# spotwelder.net
KiCad netlist of a schematic drawn in EAGLE
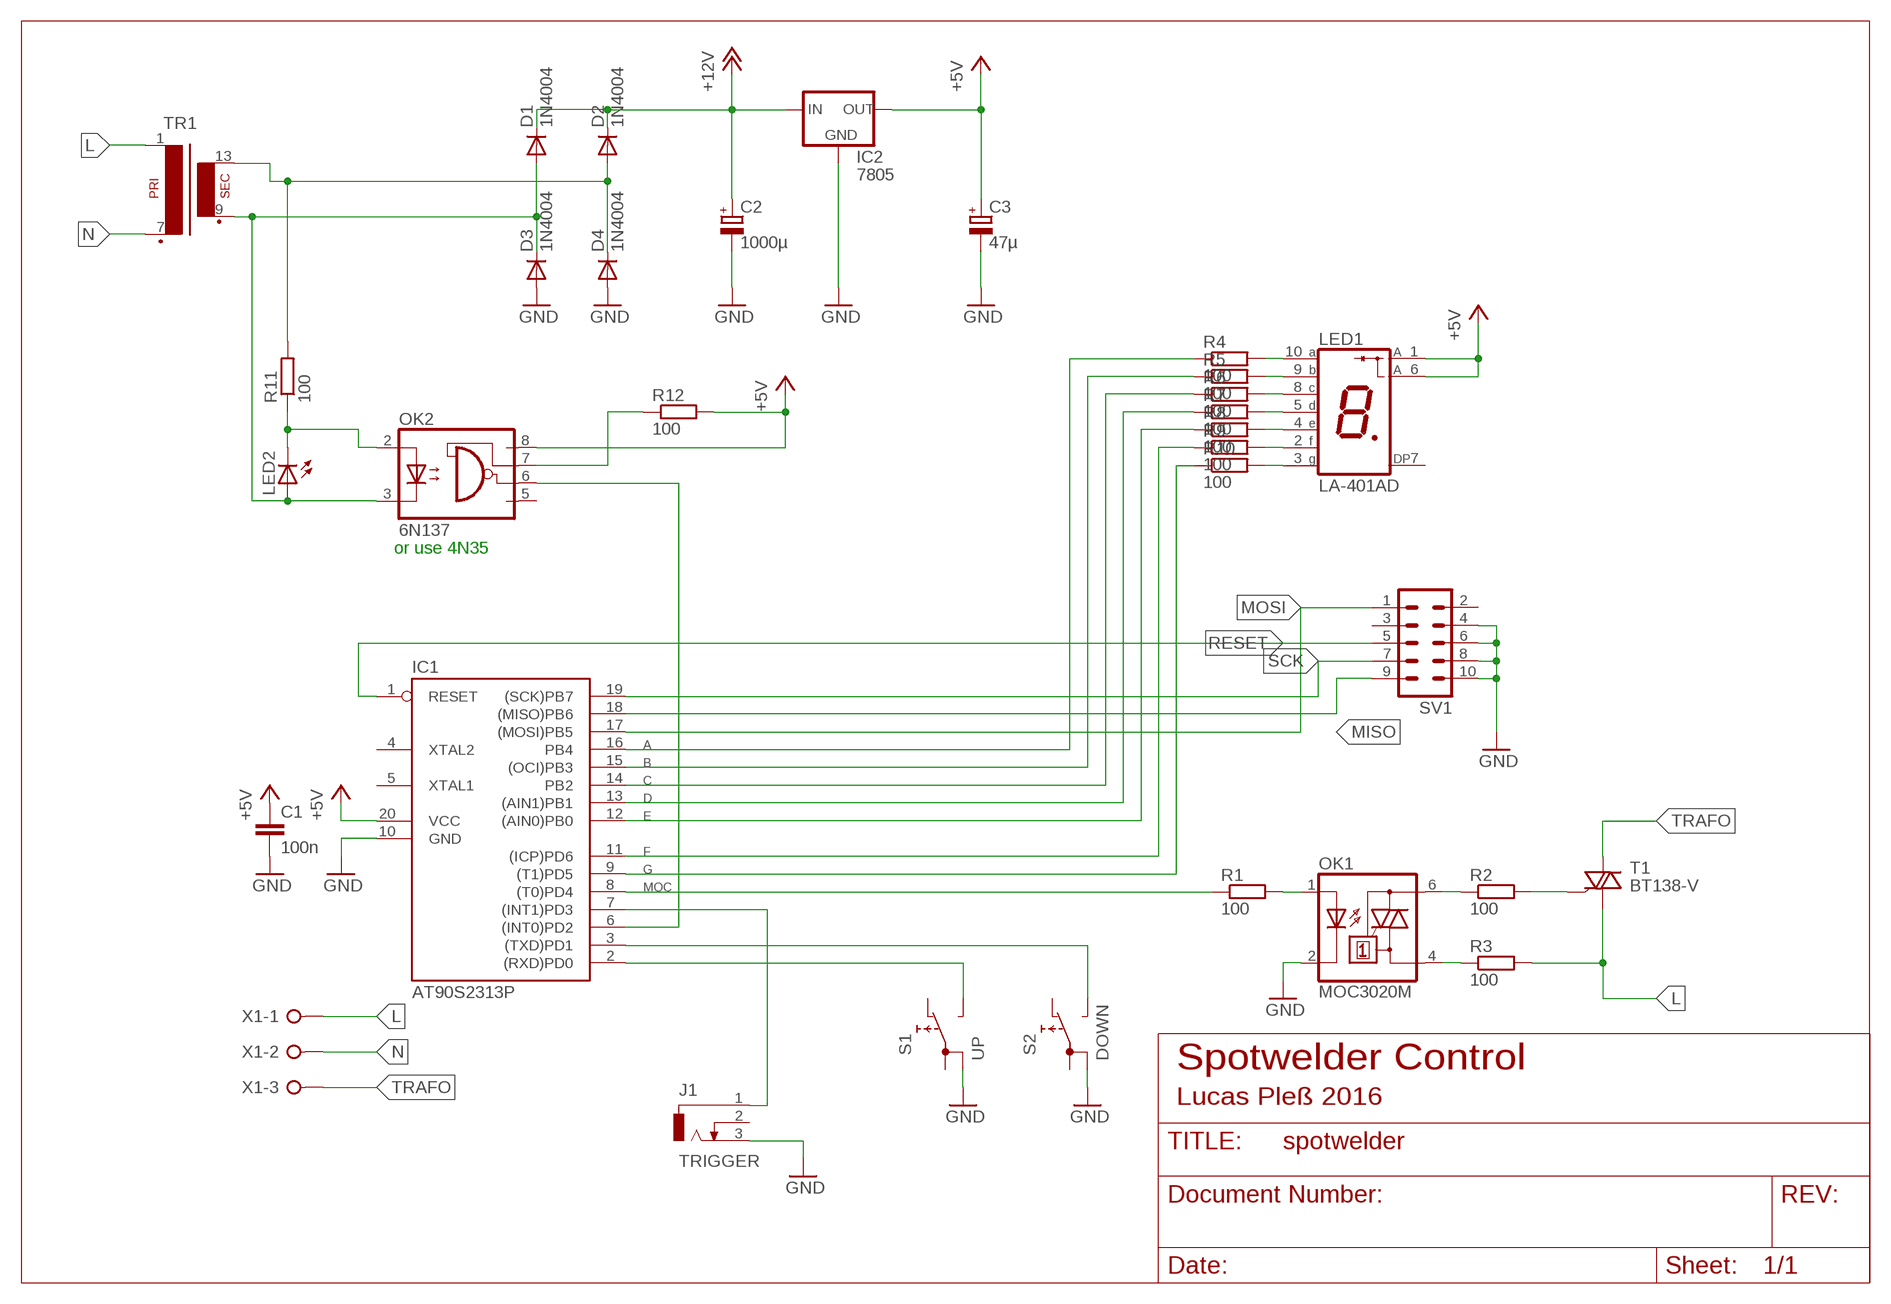
[diagram p0: schematic, sheet 1]

(export (version "E")
  (design (tool "Eeschema 10.0.6"))
  (components
    (comp (ref "C1")
      (value "100n")
      (footprint "eagle-import:C025-025X050")
      (libsource (lib "eagle-import") (part "C-EU025-025X050"))
    )
    (comp (ref "C2")
      (value "1000µ")
      (footprint "eagle-import:E2,5-5")
      (libsource (lib "eagle-import") (part "CPOL-EUE2.5-5"))
    )
    (comp (ref "C3")
      (value "47µ")
      (footprint "eagle-import:E2,5-5")
      (libsource (lib "eagle-import") (part "CPOL-EUE2.5-5"))
    )
    (comp (ref "D1")
      (value "1N4004")
      (footprint "eagle-import:DO41-10")
      (libsource (lib "eagle-import") (part "1N4004"))
    )
    (comp (ref "D2")
      (value "1N4004")
      (footprint "eagle-import:DO41-10")
      (libsource (lib "eagle-import") (part "1N4004"))
    )
    (comp (ref "D3")
      (value "1N4004")
      (footprint "eagle-import:DO41-10")
      (libsource (lib "eagle-import") (part "1N4004"))
    )
    (comp (ref "D4")
      (value "1N4004")
      (footprint "eagle-import:DO41-10")
      (libsource (lib "eagle-import") (part "1N4004"))
    )
    (comp (ref "IC1")
      (value "AT90S2313P")
      (footprint "eagle-import:DIL20")
      (libsource (lib "eagle-import") (part "AT90S2313P"))
    )
    (comp (ref "IC2")
      (value "7805")
      (footprint "eagle-import:78XXS")
      (libsource (lib "eagle-import") (part "78XXS"))
    )
    (comp (ref "J1")
      (value "TRIGGER")
      (footprint "eagle-import:DCJ0202")
      (libsource (lib "eagle-import") (part "DCJ0202"))
    )
    (comp (ref "LED1")
      (value "LA-401AD")
      (footprint "eagle-import:LA-401")
      (libsource (lib "eagle-import") (part "LA-401DA"))
    )
    (comp (ref "LED2")
      (value "LED5MM")
      (footprint "eagle-import:LED5MM")
      (libsource (lib "eagle-import") (part "LED5MM"))
    )
    (comp (ref "OK1")
      (value "MOC3020M")
      (footprint "eagle-import:DIL06")
      (fields (field (name "MF") "FAIRCHILD SEMICONDUCTOR") (field (name "MPN") "MOC3020-M"))
      (libsource (lib "eagle-import") (part "MOC30M20"))
    )
    (comp (ref "OK2")
      (value "6N137")
      (footprint "eagle-import:DIL08")
      (libsource (lib "eagle-import") (part "6N137"))
    )
    (comp (ref "R1")
      (value "100")
      (footprint "eagle-import:0207_10")
      (libsource (lib "eagle-import") (part "R-EU_0207/10"))
    )
    (comp (ref "R2")
      (value "100")
      (footprint "eagle-import:0207_10")
      (libsource (lib "eagle-import") (part "R-EU_0207/10"))
    )
    (comp (ref "R3")
      (value "100")
      (footprint "eagle-import:0207_10")
      (libsource (lib "eagle-import") (part "R-EU_0207/10"))
    )
    (comp (ref "R4")
      (value "100")
      (footprint "eagle-import:0207_10")
      (libsource (lib "eagle-import") (part "R-EU_0207/10"))
    )
    (comp (ref "R5")
      (value "100")
      (footprint "eagle-import:0207_10")
      (libsource (lib "eagle-import") (part "R-EU_0207/10"))
    )
    (comp (ref "R6")
      (value "100")
      (footprint "eagle-import:0207_10")
      (libsource (lib "eagle-import") (part "R-EU_0207/10"))
    )
    (comp (ref "R7")
      (value "100")
      (footprint "eagle-import:0207_10")
      (libsource (lib "eagle-import") (part "R-EU_0207/10"))
    )
    (comp (ref "R8")
      (value "100")
      (footprint "eagle-import:0207_10")
      (libsource (lib "eagle-import") (part "R-EU_0207/10"))
    )
    (comp (ref "R9")
      (value "100")
      (footprint "eagle-import:0207_10")
      (libsource (lib "eagle-import") (part "R-EU_0207/10"))
    )
    (comp (ref "R10")
      (value "100")
      (footprint "eagle-import:0207_10")
      (libsource (lib "eagle-import") (part "R-EU_0207/10"))
    )
    (comp (ref "R11")
      (value "100")
      (footprint "eagle-import:0207_10")
      (libsource (lib "eagle-import") (part "R-EU_0207/10"))
    )
    (comp (ref "R12")
      (value "100")
      (footprint "eagle-import:0207_10")
      (libsource (lib "eagle-import") (part "R-EU_0207/10"))
    )
    (comp (ref "S1")
      (value "UP")
      (footprint "eagle-import:5501")
      (libsource (lib "eagle-import") (part "55?01"))
    )
    (comp (ref "S2")
      (value "DOWN")
      (footprint "eagle-import:5501")
      (libsource (lib "eagle-import") (part "55?01"))
    )
    (comp (ref "SV1")
      (value "ML10")
      (footprint "eagle-import:ML10")
      (libsource (lib "eagle-import") (part "ML10"))
    )
    (comp (ref "T1")
      (value "BT138-V")
      (footprint "eagle-import:TO220BV")
      (libsource (lib "eagle-import") (part "BT138-V"))
    )
    (comp (ref "TR1")
      (value "EI60-1")
      (footprint "eagle-import:EI60-1")
      (libsource (lib "eagle-import") (part "EI60-1"))
    )
    (comp (ref "X1")
      (value "W237-3E")
      (footprint "eagle-import:W237-3E")
      (libsource (lib "eagle-import") (part "W237-3E"))
    )
  )
  (nets
    (net (code "1") (name "+5V") (class "Default")
      (node (ref "C1") (pin "1") (pinfunction "1_1") (pintype "passive"))
      (node (ref "C3") (pin "+") (pinfunction "+_+") (pintype "passive"))
      (node (ref "IC1") (pin "20") (pinfunction "VCC_20") (pintype "power_in"))
      (node (ref "IC2") (pin "OUT") (pinfunction "OUT_OUT") (pintype "passive"))
      (node (ref "LED1") (pin "1") (pinfunction "A_1") (pintype "passive"))
      (node (ref "LED1") (pin "6") (pinfunction "A_6") (pintype "passive"))
      (node (ref "OK2") (pin "8") (pinfunction "VCC_8") (pintype "passive"))
      (node (ref "R12") (pin "2") (pinfunction "2_2") (pintype "passive"))
    )
    (net (code "2") (name "+12V") (class "Default")
      (node (ref "C2") (pin "+") (pinfunction "+_+") (pintype "passive"))
      (node (ref "D1") (pin "C") (pinfunction "C_C") (pintype "passive"))
      (node (ref "D2") (pin "C") (pinfunction "C_C") (pintype "passive"))
      (node (ref "IC2") (pin "IN") (pinfunction "IN_IN") (pintype "input"))
    )
    (net (code "3") (name "/A") (class "Default")
      (node (ref "IC1") (pin "16") (pinfunction "PB4_16") (pintype "bidirectional"))
      (node (ref "R4") (pin "1") (pinfunction "1_1") (pintype "passive"))
    )
    (net (code "4") (name "/B") (class "Default")
      (node (ref "IC1") (pin "15") (pinfunction "(OCI)PB3_15") (pintype "bidirectional"))
      (node (ref "R5") (pin "1") (pinfunction "1_1") (pintype "passive"))
    )
    (net (code "5") (name "/C") (class "Default")
      (node (ref "IC1") (pin "14") (pinfunction "PB2_14") (pintype "bidirectional"))
      (node (ref "R6") (pin "1") (pinfunction "1_1") (pintype "passive"))
    )
    (net (code "6") (name "/D") (class "Default")
      (node (ref "IC1") (pin "13") (pinfunction "(AIN1)PB1_13") (pintype "bidirectional"))
      (node (ref "R7") (pin "1") (pinfunction "1_1") (pintype "passive"))
    )
    (net (code "7") (name "/E") (class "Default")
      (node (ref "IC1") (pin "12") (pinfunction "(AIN0)PB0_12") (pintype "bidirectional"))
      (node (ref "R8") (pin "1") (pinfunction "1_1") (pintype "passive"))
    )
    (net (code "8") (name "/F") (class "Default")
      (node (ref "IC1") (pin "11") (pinfunction "(ICP)PD6_11") (pintype "bidirectional"))
      (node (ref "R9") (pin "1") (pinfunction "1_1") (pintype "passive"))
    )
    (net (code "9") (name "/G") (class "Default")
      (node (ref "IC1") (pin "9") (pinfunction "(T1)PD5_9") (pintype "bidirectional"))
      (node (ref "R10") (pin "1") (pinfunction "1_1") (pintype "passive"))
    )
    (net (code "10") (name "/MOC") (class "Default")
      (node (ref "IC1") (pin "8") (pinfunction "(T0)PD4_8") (pintype "bidirectional"))
      (node (ref "R1") (pin "1") (pinfunction "1_1") (pintype "passive"))
    )
    (net (code "11") (name "GND") (class "Default")
      (node (ref "C1") (pin "2") (pinfunction "2_2") (pintype "passive"))
      (node (ref "C2") (pin "-") (pinfunction "-_-") (pintype "passive"))
      (node (ref "C3") (pin "-") (pinfunction "-_-") (pintype "passive"))
      (node (ref "D3") (pin "A") (pinfunction "A_A") (pintype "passive"))
      (node (ref "D4") (pin "A") (pinfunction "A_A") (pintype "passive"))
      (node (ref "IC1") (pin "10") (pinfunction "GND_10") (pintype "power_in"))
      (node (ref "IC2") (pin "GND") (pinfunction "GND_GND") (pintype "input"))
      (node (ref "J1") (pin "3") (pinfunction "3_3") (pintype "passive"))
      (node (ref "OK1") (pin "2") (pinfunction "C_2") (pintype "passive"))
      (node (ref "S1") (pin "1B") (pinfunction "1B_1B") (pintype "passive"))
      (node (ref "S2") (pin "1B") (pinfunction "1B_1B") (pintype "passive"))
      (node (ref "SV1") (pin "10") (pinfunction "10_10") (pintype "passive"))
      (node (ref "SV1") (pin "4") (pinfunction "4_4") (pintype "passive"))
      (node (ref "SV1") (pin "6") (pinfunction "6_6") (pintype "passive"))
      (node (ref "SV1") (pin "8") (pinfunction "8_8") (pintype "passive"))
    )
    (net (code "12") (name "L") (class "Default")
      (node (ref "R3") (pin "2") (pinfunction "2_2") (pintype "passive"))
      (node (ref "T1") (pin "T1") (pinfunction "A1_T1") (pintype "passive"))
      (node (ref "TR1") (pin "1") (pinfunction "P1_1") (pintype "passive"))
      (node (ref "X1") (pin "1") (pinfunction "KL_1") (pintype "passive"))
    )
    (net (code "13") (name "MISO") (class "Default")
      (node (ref "IC1") (pin "18") (pinfunction "(MISO)PB6_18") (pintype "bidirectional"))
      (node (ref "SV1") (pin "9") (pinfunction "9_9") (pintype "passive"))
    )
    (net (code "14") (name "MOSI") (class "Default")
      (node (ref "IC1") (pin "17") (pinfunction "(MOSI)PB5_17") (pintype "bidirectional"))
      (node (ref "SV1") (pin "1") (pinfunction "1_1") (pintype "passive"))
    )
    (net (code "15") (name "N") (class "Default")
      (node (ref "TR1") (pin "7") (pinfunction "P2_7") (pintype "passive"))
      (node (ref "X1") (pin "2") (pinfunction "KL_2") (pintype "passive"))
    )
    (net (code "16") (name "Net-(IC1-(INT0)PD2)") (class "Default")
      (node (ref "IC1") (pin "6") (pinfunction "(INT0)PD2_6") (pintype "bidirectional"))
      (node (ref "OK2") (pin "6") (pinfunction "VO_6") (pintype "passive"))
    )
    (net (code "17") (name "Net-(IC1-(INT1)PD3)") (class "Default")
      (node (ref "IC1") (pin "7") (pinfunction "(INT1)PD3_7") (pintype "bidirectional"))
      (node (ref "J1") (pin "1") (pinfunction "1_1") (pintype "passive"))
    )
    (net (code "18") (name "Net-(IC1-(RXD)PD0)") (class "Default")
      (node (ref "IC1") (pin "2") (pinfunction "(RXD)PD0_2") (pintype "bidirectional"))
      (node (ref "S1") (pin "NO") (pinfunction "NO_NO") (pintype "passive"))
    )
    (net (code "19") (name "Net-(IC1-(TXD)PD1)") (class "Default")
      (node (ref "IC1") (pin "3") (pinfunction "(TXD)PD1_3") (pintype "bidirectional"))
      (node (ref "S2") (pin "NO") (pinfunction "NO_NO") (pintype "passive"))
    )
    (net (code "20") (name "Net-(LED1-A-Pad10)") (class "Default")
      (node (ref "LED1") (pin "10") (pinfunction "A_10") (pintype "passive"))
      (node (ref "R4") (pin "2") (pinfunction "2_2") (pintype "passive"))
    )
    (net (code "21") (name "Net-(LED1-B)") (class "Default")
      (node (ref "LED1") (pin "9") (pinfunction "B_9") (pintype "passive"))
      (node (ref "R5") (pin "2") (pinfunction "2_2") (pintype "passive"))
    )
    (net (code "22") (name "Net-(LED1-C)") (class "Default")
      (node (ref "LED1") (pin "8") (pinfunction "C_8") (pintype "passive"))
      (node (ref "R6") (pin "2") (pinfunction "2_2") (pintype "passive"))
    )
    (net (code "23") (name "Net-(LED1-D)") (class "Default")
      (node (ref "LED1") (pin "5") (pinfunction "D_5") (pintype "passive"))
      (node (ref "R7") (pin "2") (pinfunction "2_2") (pintype "passive"))
    )
    (net (code "24") (name "Net-(LED1-E)") (class "Default")
      (node (ref "LED1") (pin "4") (pinfunction "E_4") (pintype "passive"))
      (node (ref "R8") (pin "2") (pinfunction "2_2") (pintype "passive"))
    )
    (net (code "25") (name "Net-(LED1-F)") (class "Default")
      (node (ref "LED1") (pin "2") (pinfunction "F_2") (pintype "passive"))
      (node (ref "R9") (pin "2") (pinfunction "2_2") (pintype "passive"))
    )
    (net (code "26") (name "Net-(LED1-G)") (class "Default")
      (node (ref "LED1") (pin "3") (pinfunction "G_3") (pintype "passive"))
      (node (ref "R10") (pin "2") (pinfunction "2_2") (pintype "passive"))
    )
    (net (code "27") (name "Net-(LED2-C)") (class "Default")
      (node (ref "LED2") (pin "K") (pinfunction "C_K") (pintype "passive"))
      (node (ref "OK2") (pin "2") (pinfunction "A_2") (pintype "passive"))
      (node (ref "R11") (pin "1") (pinfunction "1_1") (pintype "passive"))
    )
    (net (code "28") (name "Net-(OK1-A)") (class "Default")
      (node (ref "OK1") (pin "1") (pinfunction "A_1") (pintype "passive"))
      (node (ref "R1") (pin "2") (pinfunction "2_2") (pintype "passive"))
    )
    (net (code "29") (name "Net-(OK1-A1)") (class "Default")
      (node (ref "OK1") (pin "4") (pinfunction "A1_4") (pintype "passive"))
      (node (ref "R3") (pin "1") (pinfunction "1_1") (pintype "passive"))
    )
    (net (code "30") (name "Net-(OK1-A2)") (class "Default")
      (node (ref "OK1") (pin "6") (pinfunction "A2_6") (pintype "passive"))
      (node (ref "R2") (pin "1") (pinfunction "1_1") (pintype "passive"))
    )
    (net (code "31") (name "Net-(OK2-C)") (class "Default")
      (node (ref "D1") (pin "A") (pinfunction "A_A") (pintype "passive"))
      (node (ref "D3") (pin "C") (pinfunction "C_C") (pintype "passive"))
      (node (ref "LED2") (pin "A") (pinfunction "A_A") (pintype "passive"))
      (node (ref "OK2") (pin "3") (pinfunction "C_3") (pintype "passive"))
      (node (ref "TR1") (pin "9") (pinfunction "S3_9") (pintype "passive"))
    )
    (net (code "32") (name "Net-(OK2-VE)") (class "Default")
      (node (ref "OK2") (pin "7") (pinfunction "VE_7") (pintype "passive"))
      (node (ref "R12") (pin "1") (pinfunction "1_1") (pintype "passive"))
    )
    (net (code "33") (name "Net-(R2-Pad2)") (class "Default")
      (node (ref "R2") (pin "2") (pinfunction "2_2") (pintype "passive"))
      (node (ref "T1") (pin "G") (pinfunction "G_G") (pintype "passive"))
    )
    (net (code "34") (name "Net-(TR1-S4)") (class "Default")
      (node (ref "D2") (pin "A") (pinfunction "A_A") (pintype "passive"))
      (node (ref "D4") (pin "C") (pinfunction "C_C") (pintype "passive"))
      (node (ref "R11") (pin "2") (pinfunction "2_2") (pintype "passive"))
      (node (ref "TR1") (pin "13") (pinfunction "S4_13") (pintype "passive"))
    )
    (net (code "35") (name "RESET") (class "Default")
      (node (ref "IC1") (pin "1") (pinfunction "RESET_1") (pintype "bidirectional"))
      (node (ref "SV1") (pin "5") (pinfunction "5_5") (pintype "passive"))
    )
    (net (code "36") (name "SCK") (class "Default")
      (node (ref "IC1") (pin "19") (pinfunction "(SCK)PB7_19") (pintype "bidirectional"))
      (node (ref "SV1") (pin "7") (pinfunction "7_7") (pintype "passive"))
    )
    (net (code "37") (name "TRAFO") (class "Default")
      (node (ref "T1") (pin "T2") (pinfunction "A2_T2") (pintype "passive"))
      (node (ref "X1") (pin "3") (pinfunction "KL_3") (pintype "passive"))
    )
    (net (code "38") (name "unconnected-(IC1-XTAL1-Pad5)") (class "Default")
      (node (ref "IC1") (pin "5") (pinfunction "XTAL1_5") (pintype "bidirectional"))
    )
    (net (code "39") (name "unconnected-(IC1-XTAL2-Pad4)") (class "Default")
      (node (ref "IC1") (pin "4") (pinfunction "XTAL2_4") (pintype "bidirectional"))
    )
    (net (code "40") (name "unconnected-(J1-Pad2)") (class "Default")
      (node (ref "J1") (pin "2") (pinfunction "2_2") (pintype "passive"))
    )
    (net (code "41") (name "unconnected-(LED1-DP-Pad7)") (class "Default")
      (node (ref "LED1") (pin "7") (pinfunction "DP_7") (pintype "passive"))
    )
    (net (code "42") (name "unconnected-(OK2-GND-Pad5)") (class "Default")
      (node (ref "OK2") (pin "5") (pinfunction "GND_5") (pintype "passive"))
    )
    (net (code "43") (name "unconnected-(S1-Pad1A)") (class "Default")
      (node (ref "S1") (pin "1A") (pinfunction "1A_1A") (pintype "passive"))
    )
    (net (code "44") (name "unconnected-(S1-PadNC)") (class "Default")
      (node (ref "S1") (pin "NC") (pinfunction "NC_NC") (pintype "passive"))
    )
    (net (code "45") (name "unconnected-(S2-Pad1A)") (class "Default")
      (node (ref "S2") (pin "1A") (pinfunction "1A_1A") (pintype "passive"))
    )
    (net (code "46") (name "unconnected-(S2-PadNC)") (class "Default")
      (node (ref "S2") (pin "NC") (pinfunction "NC_NC") (pintype "passive"))
    )
    (net (code "47") (name "unconnected-(SV1-Pad2)") (class "Default")
      (node (ref "SV1") (pin "2") (pinfunction "2_2") (pintype "passive"))
    )
    (net (code "48") (name "unconnected-(SV1-Pad3)") (class "Default")
      (node (ref "SV1") (pin "3") (pinfunction "3_3") (pintype "passive"))
    )
  )
)
